# tiny412.net
KiCad netlist of a schematic drawn in EAGLE
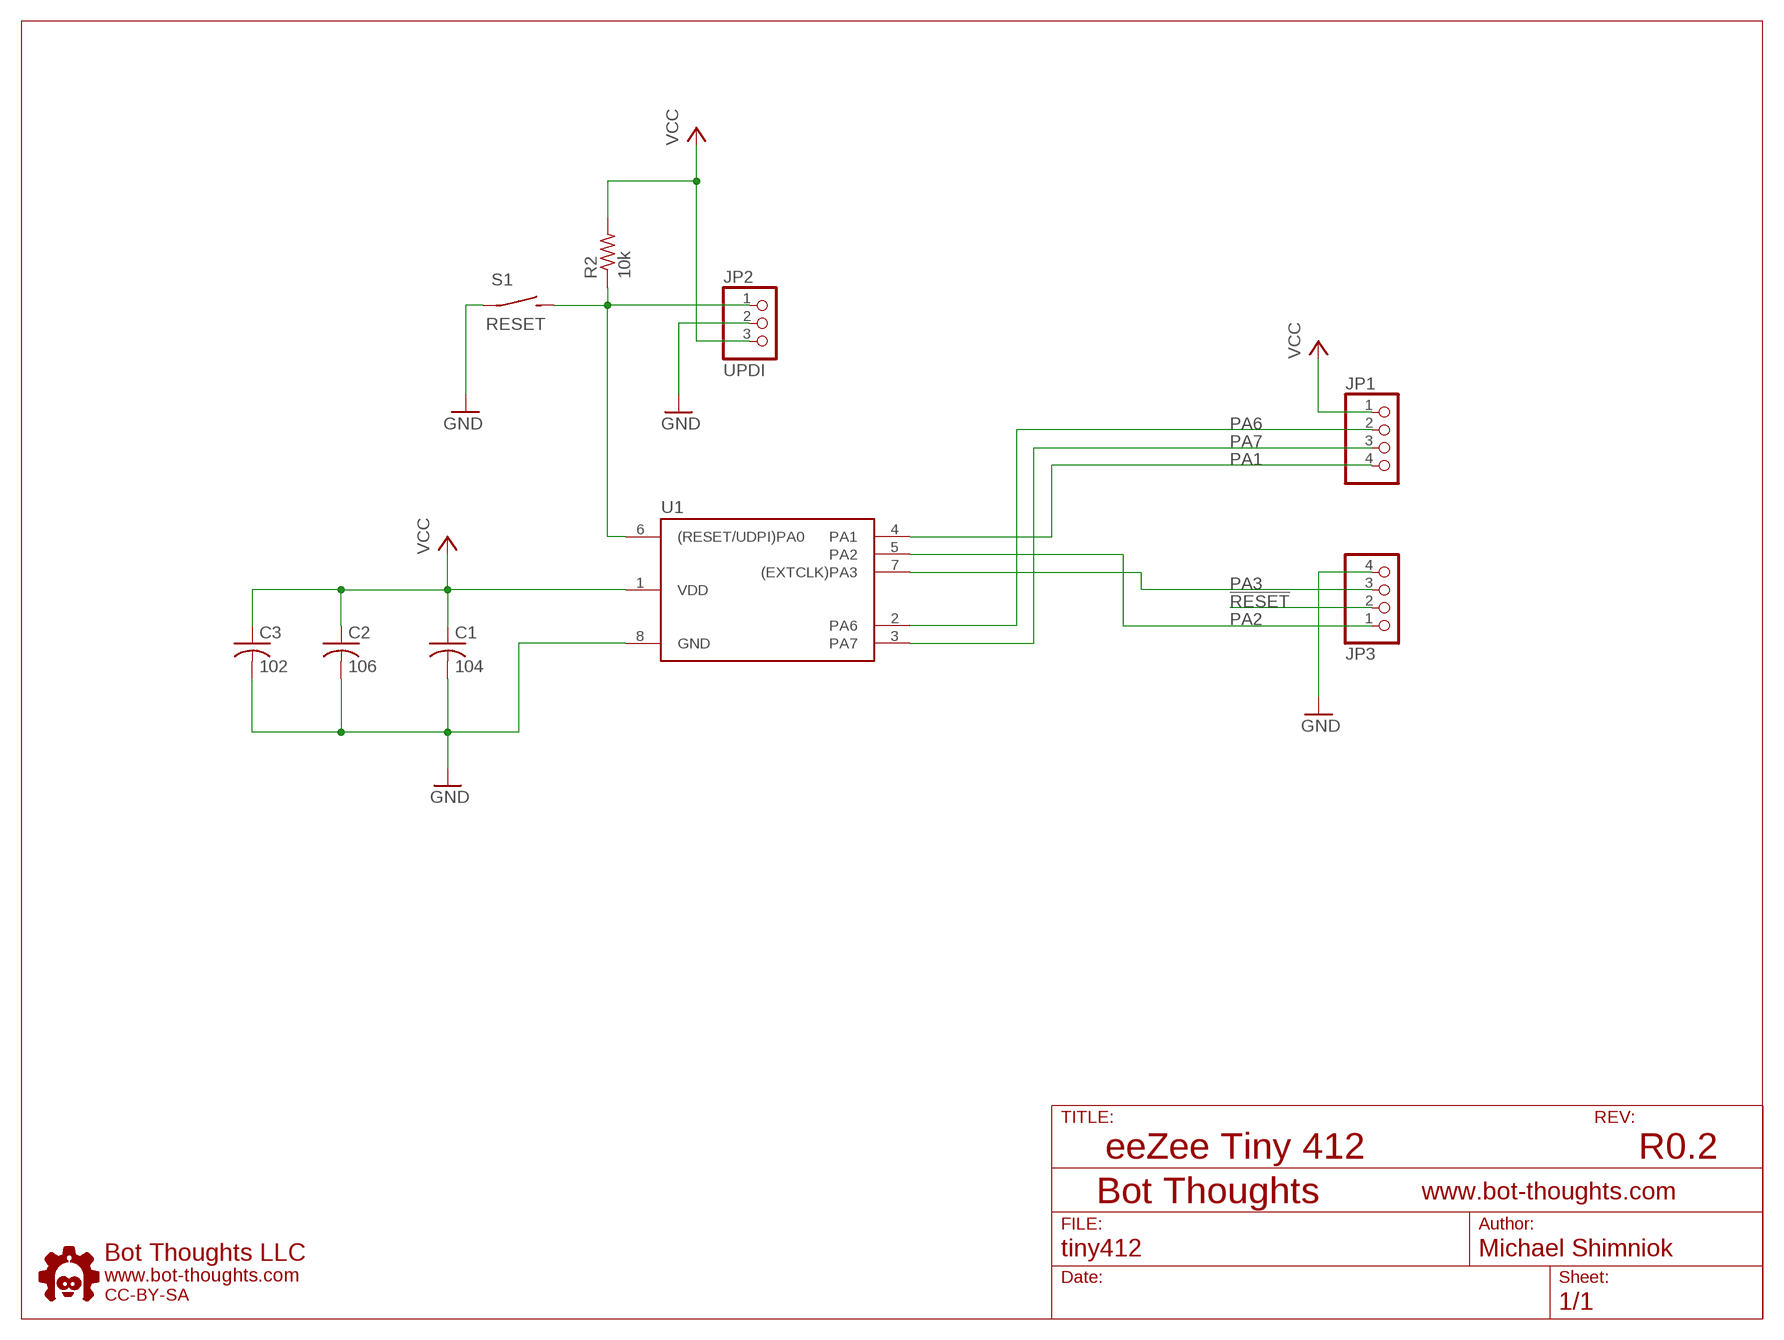
[diagram p0: schematic, sheet 1]

(export (version "E")
  (design (tool "Eeschema 10.0.6"))
  (components
    (comp (ref "C1")
      (value "104")
      (footprint "eagle-import:C0603")
      (fields (field (name "PARTNO") "0603YC104KAT2A"))
      (libsource (lib "eagle-import") (part "C-USC0603"))
    )
    (comp (ref "C2")
      (value "106")
      (footprint "eagle-import:0603")
      (fields (field (name "PARTNO") "MCTT21X106M6R3CT"))
      (libsource (lib "eagle-import") (part "C-0603"))
    )
    (comp (ref "C3")
      (value "102")
      (footprint "eagle-import:C0603")
      (fields (field (name "PARTNO") "0603YC104KAT2A"))
      (libsource (lib "eagle-import") (part "C-USC0603"))
    )
    (comp (ref "JP1")
      (value "PINHD-1X04_2.54-S")
      (footprint "eagle-import:1X04-S")
      (libsource (lib "eagle-import") (part "PINHD-1X04_2.54-S"))
    )
    (comp (ref "JP2")
      (value "UPDI")
      (footprint "eagle-import:1X03-S")
      (libsource (lib "eagle-import") (part "PINHD-1X03_2.54-S"))
    )
    (comp (ref "JP3")
      (value "PINHD-1X04_2.54-S")
      (footprint "eagle-import:1X04-S")
      (libsource (lib "eagle-import") (part "PINHD-1X04_2.54-S"))
    )
    (comp (ref "R2")
      (value "10k")
      (footprint "eagle-import:R0603")
      (fields (field (name "PARTNO") "ERJ-3GEYJ103V"))
      (libsource (lib "eagle-import") (part "R-US_R0603"))
    )
    (comp (ref "S1")
      (value "RESET")
      (footprint "eagle-import:3X4X2TACT")
      (libsource (lib "eagle-import") (part "SPST_3X4X2"))
    )
    (comp (ref "U$1")
      (value "BTLOGO-LOGO-MD")
      (footprint "eagle-import:BTLOGOM")
      (libsource (lib "eagle-import") (part "BTLOGO-LOGO-MD"))
    )
    (comp (ref "U1")
      (value "ATTINY212/412")
      (footprint "eagle-import:SOIC8N")
      (libsource (lib "eagle-import") (part "ATTINY212/412"))
    )
  )
  (nets
    (net (code "1") (name "/PA1") (class "Default")
      (node (ref "JP1") (pin "4") (pinfunction "4_4") (pintype "passive"))
      (node (ref "U1") (pin "4") (pinfunction "PA1_4") (pintype "bidirectional"))
    )
    (net (code "2") (name "/PA2") (class "Default")
      (node (ref "JP3") (pin "1") (pinfunction "1_1") (pintype "passive"))
      (node (ref "U1") (pin "5") (pinfunction "PA2_5") (pintype "bidirectional"))
    )
    (net (code "3") (name "/PA3") (class "Default")
      (node (ref "JP3") (pin "3") (pinfunction "3_3") (pintype "passive"))
      (node (ref "U1") (pin "7") (pinfunction "(EXTCLK)PA3_7") (pintype "bidirectional"))
    )
    (net (code "4") (name "/PA6") (class "Default")
      (node (ref "JP1") (pin "2") (pinfunction "2_2") (pintype "passive"))
      (node (ref "U1") (pin "2") (pinfunction "PA6_2") (pintype "bidirectional"))
    )
    (net (code "5") (name "/PA7") (class "Default")
      (node (ref "JP1") (pin "3") (pinfunction "3_3") (pintype "passive"))
      (node (ref "U1") (pin "3") (pinfunction "PA7_3") (pintype "bidirectional"))
    )
    (net (code "6") (name "/~{RESET}") (class "Default")
      (node (ref "JP2") (pin "1") (pinfunction "1_1") (pintype "passive"))
      (node (ref "JP3") (pin "2") (pinfunction "2_2") (pintype "passive"))
      (node (ref "R2") (pin "1") (pinfunction "1_1") (pintype "passive"))
      (node (ref "S1") (pin "P$2") (pinfunction "S_P$2") (pintype "passive"))
      (node (ref "U1") (pin "6") (pinfunction "(RESET/UDPI)PA0_6") (pintype "bidirectional"))
    )
    (net (code "7") (name "GND") (class "Default")
      (node (ref "C1") (pin "2") (pinfunction "2_2") (pintype "passive"))
      (node (ref "C2") (pin "2") (pinfunction "-_2") (pintype "passive"))
      (node (ref "C3") (pin "2") (pinfunction "2_2") (pintype "passive"))
      (node (ref "JP2") (pin "2") (pinfunction "2_2") (pintype "passive"))
      (node (ref "JP3") (pin "4") (pinfunction "4_4") (pintype "passive"))
      (node (ref "S1") (pin "P$1") (pinfunction "P_P$1") (pintype "passive"))
      (node (ref "U1") (pin "8") (pinfunction "GND_8") (pintype "power_in"))
    )
    (net (code "8") (name "VCC") (class "Default")
      (node (ref "C1") (pin "1") (pinfunction "1_1") (pintype "passive"))
      (node (ref "C2") (pin "1") (pinfunction "+_1") (pintype "passive"))
      (node (ref "C3") (pin "1") (pinfunction "1_1") (pintype "passive"))
      (node (ref "JP1") (pin "1") (pinfunction "1_1") (pintype "passive"))
      (node (ref "JP2") (pin "3") (pinfunction "3_3") (pintype "passive"))
      (node (ref "R2") (pin "2") (pinfunction "2_2") (pintype "passive"))
      (node (ref "U1") (pin "1") (pinfunction "VDD_1") (pintype "power_in"))
    )
  )
)
